# PMT_AMP_J000331REVH.net
KiCad netlist of a schematic drawn in EAGLE
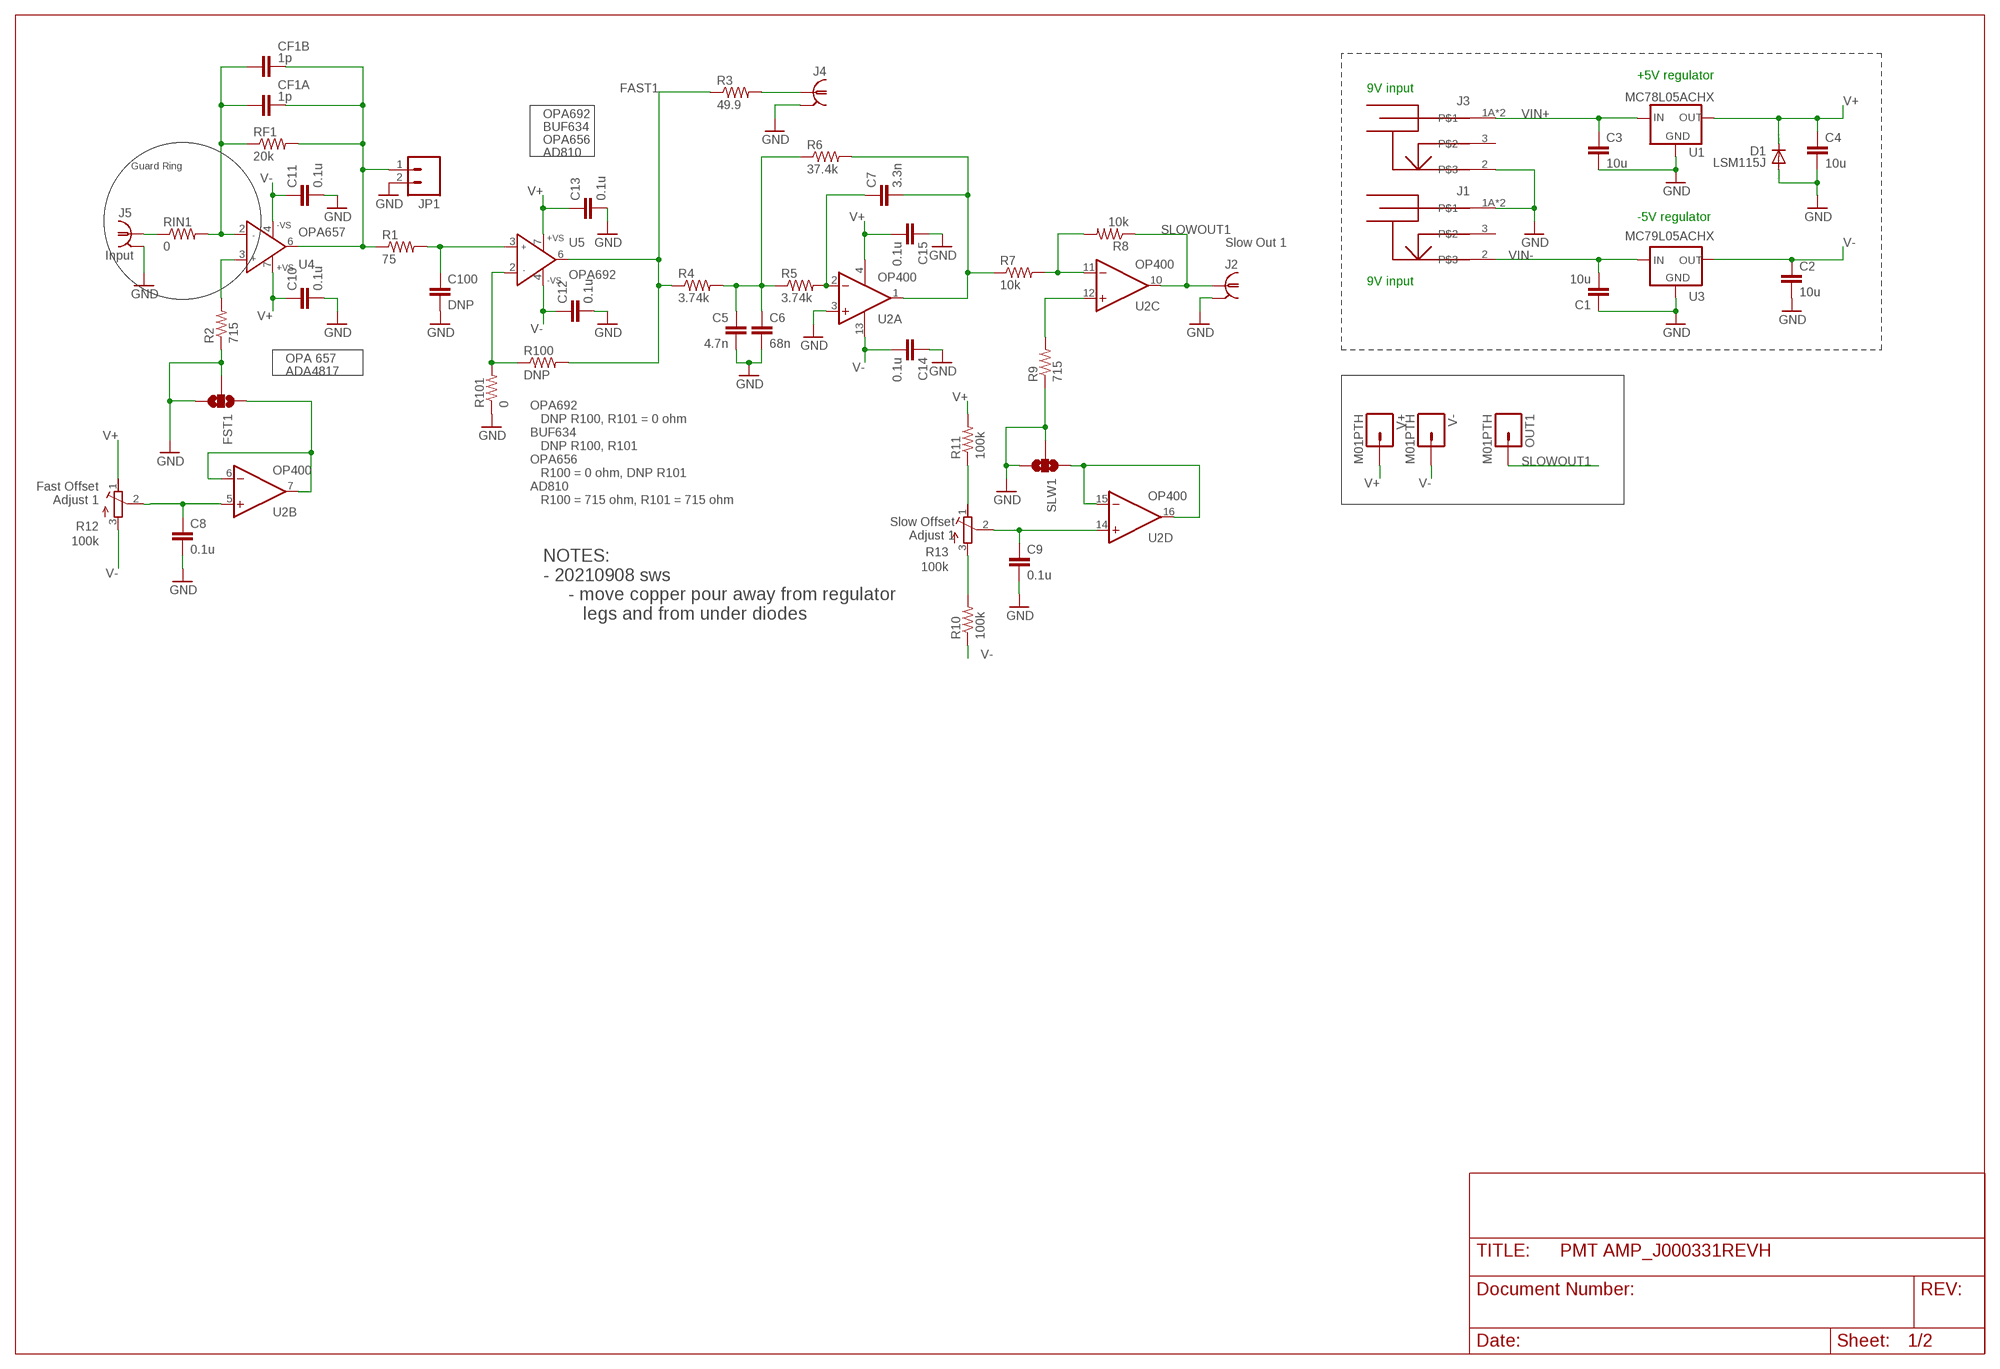
[diagram p0: schematic, sheet 1]
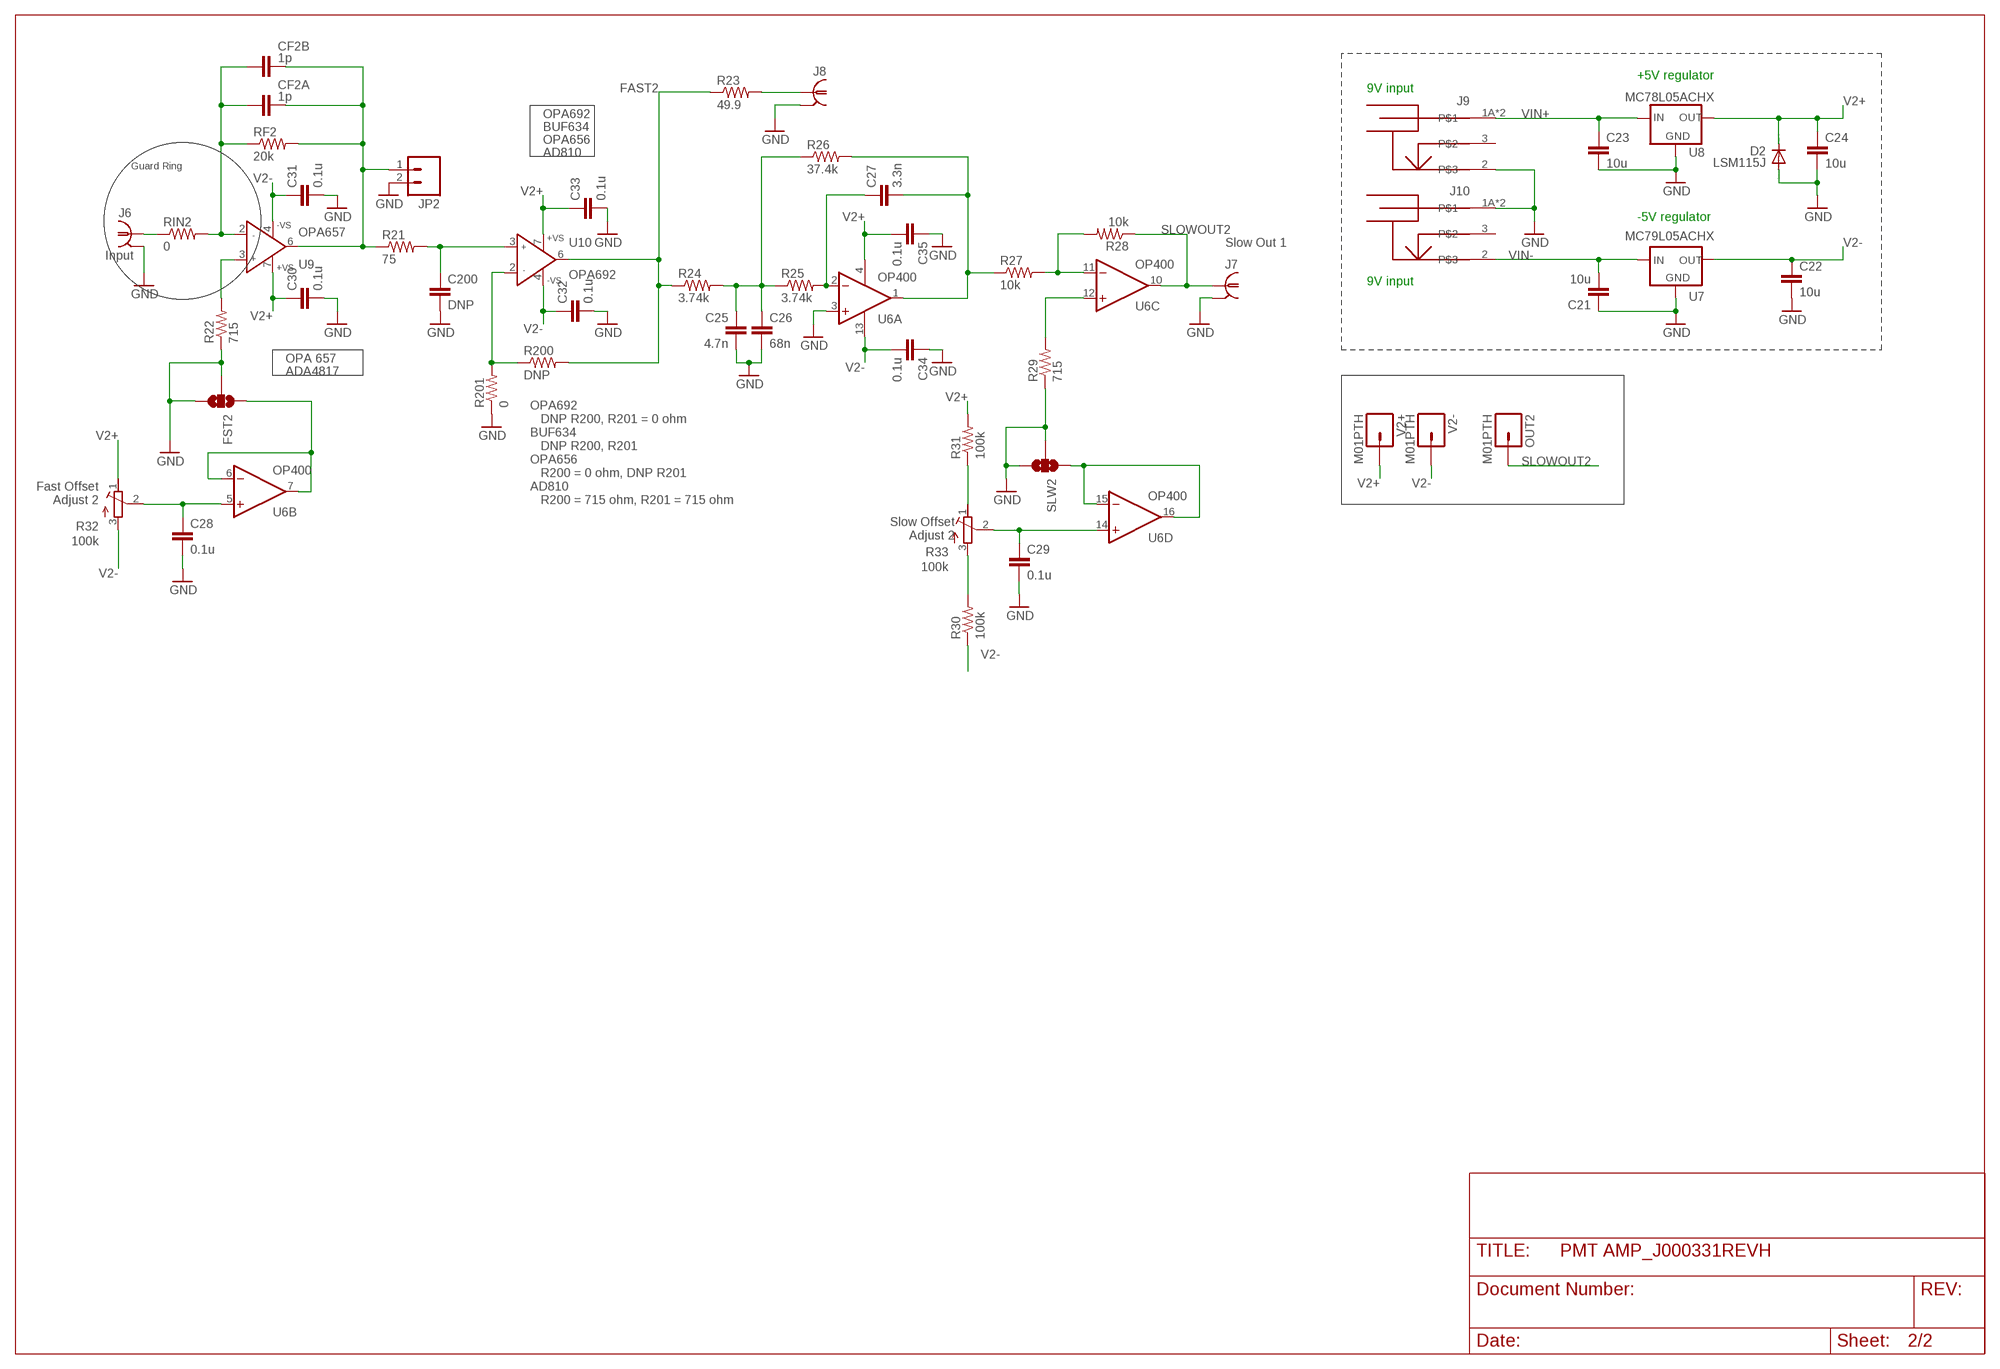
[diagram p1: schematic, sheet 2]

(export (version "E")
  (design (tool "Eeschema 10.0.6"))
  (components
    (comp (ref "C21")
      (value "10u")
      (footprint "eagle-import:C1206")
      (libsource (lib "eagle-import") (part "C-EUC1206"))
    )
    (comp (ref "C22")
      (value "10u")
      (footprint "eagle-import:C1206")
      (libsource (lib "eagle-import") (part "C-EUC1206"))
    )
    (comp (ref "C23")
      (value "10u")
      (footprint "eagle-import:C1206")
      (libsource (lib "eagle-import") (part "C-EUC1206"))
    )
    (comp (ref "C24")
      (value "10u")
      (footprint "eagle-import:C1206")
      (libsource (lib "eagle-import") (part "C-EUC1206"))
    )
    (comp (ref "C25")
      (value "4.7n")
      (footprint "eagle-import:C0805")
      (libsource (lib "eagle-import") (part "C-EUC0805"))
    )
    (comp (ref "C26")
      (value "68n")
      (footprint "eagle-import:C0805")
      (libsource (lib "eagle-import") (part "C-EUC0805"))
    )
    (comp (ref "C27")
      (value "3.3n")
      (footprint "eagle-import:C0805")
      (libsource (lib "eagle-import") (part "C-EUC0805"))
    )
    (comp (ref "C28")
      (value "0.1u")
      (footprint "eagle-import:C0603")
      (libsource (lib "eagle-import") (part "C-EUC0603"))
    )
    (comp (ref "C29")
      (value "0.1u")
      (footprint "eagle-import:C0603")
      (libsource (lib "eagle-import") (part "C-EUC0603"))
    )
    (comp (ref "C30")
      (value "0.1u")
      (footprint "eagle-import:C0603")
      (libsource (lib "eagle-import") (part "C-EUC0603"))
    )
    (comp (ref "C31")
      (value "0.1u")
      (footprint "eagle-import:C0603")
      (libsource (lib "eagle-import") (part "C-EUC0603"))
    )
    (comp (ref "C32")
      (value "0.1u")
      (footprint "eagle-import:C0603")
      (libsource (lib "eagle-import") (part "C-EUC0603"))
    )
    (comp (ref "C33")
      (value "0.1u")
      (footprint "eagle-import:C0603")
      (libsource (lib "eagle-import") (part "C-EUC0603"))
    )
    (comp (ref "C34")
      (value "0.1u")
      (footprint "eagle-import:C0603")
      (libsource (lib "eagle-import") (part "C-EUC0603"))
    )
    (comp (ref "C35")
      (value "0.1u")
      (footprint "eagle-import:C0603")
      (libsource (lib "eagle-import") (part "C-EUC0603"))
    )
    (comp (ref "C200")
      (value "DNP")
      (footprint "eagle-import:C0805")
      (libsource (lib "eagle-import") (part "C-EUC0805"))
    )
    (comp (ref "CF2A")
      (value "1p")
      (footprint "eagle-import:C1206")
      (libsource (lib "eagle-import") (part "C-EUC1206"))
    )
    (comp (ref "CF2B")
      (value "1p")
      (footprint "eagle-import:C1206")
      (libsource (lib "eagle-import") (part "C-EUC1206"))
    )
    (comp (ref "D2")
      (value "LSM115J")
      (footprint "eagle-import:DO214BA")
      (libsource (lib "eagle-import") (part "DIODE-DO214BA"))
    )
    (comp (ref "FST2")
      (value "SOLDERJUMPER_2WAYS")
      (footprint "eagle-import:SJ_3")
      (libsource (lib "eagle-import") (part "SOLDERJUMPER_2WAYS"))
    )
    (comp (ref "J6")
      (value "1-227161-0")
      (footprint "eagle-import:AMP_227161")
      (fields
        (field (name "MF") "TYCO ELECTRONICS")
        (field (name "MPN") "1-227161")
        (field (name "MF_1") "TE")
        (field (name "MPN_1") "5413879-1")
      )
      (libsource (lib "eagle-import") (part "?2271611--0"))
    )
    (comp (ref "J7")
      (value "1-227161-0")
      (footprint "eagle-import:AMP_227161")
      (fields
        (field (name "MF") "TYCO ELECTRONICS")
        (field (name "MPN") "1-227161")
        (field (name "MF_1") "TE")
        (field (name "MPN_1") "5413879-1")
      )
      (libsource (lib "eagle-import") (part "?2271611--0"))
    )
    (comp (ref "J8")
      (value "1-227161-0")
      (footprint "eagle-import:AMP_227161")
      (fields
        (field (name "MF") "TYCO ELECTRONICS")
        (field (name "MPN") "1-227161")
        (field (name "MF_1") "TE")
        (field (name "MPN_1") "5413879-1")
      )
      (libsource (lib "eagle-import") (part "?2271611--0"))
    )
    (comp (ref "J9")
      (value "POWER_JACK_SHUNTPJ-002")
      (footprint "eagle-import:PJ-002")
      (libsource (lib "eagle-import") (part "POWER_JACK_SHUNTPJ-002"))
    )
    (comp (ref "J10")
      (value "POWER_JACK_SHUNTPJ-002")
      (footprint "eagle-import:PJ-002")
      (libsource (lib "eagle-import") (part "POWER_JACK_SHUNTPJ-002"))
    )
    (comp (ref "JP2")
      (value "M02LOCK")
      (footprint "eagle-import:1X02_LOCK")
      (libsource (lib "eagle-import") (part "M02LOCK"))
    )
    (comp (ref "OUT2")
      (value "M01PTH")
      (footprint "eagle-import:1X01")
      (libsource (lib "eagle-import") (part "M01PTH"))
    )
    (comp (ref "R21")
      (value "75")
      (footprint "eagle-import:R0805")
      (libsource (lib "eagle-import") (part "R-US_R0805"))
    )
    (comp (ref "R22")
      (value "715")
      (footprint "eagle-import:R0805")
      (libsource (lib "eagle-import") (part "R-US_R0805"))
    )
    (comp (ref "R23")
      (value "49.9")
      (footprint "eagle-import:2512LONG")
      (libsource (lib "eagle-import") (part "RESISTOR-POWER2512WIDE"))
    )
    (comp (ref "R24")
      (value "3.74k")
      (footprint "eagle-import:R0805")
      (libsource (lib "eagle-import") (part "R-US_R0805"))
    )
    (comp (ref "R25")
      (value "3.74k")
      (footprint "eagle-import:R0805")
      (libsource (lib "eagle-import") (part "R-US_R0805"))
    )
    (comp (ref "R26")
      (value "37.4k")
      (footprint "eagle-import:R0805")
      (libsource (lib "eagle-import") (part "R-US_R0805"))
    )
    (comp (ref "R27")
      (value "10k")
      (footprint "eagle-import:R0805")
      (libsource (lib "eagle-import") (part "R-US_R0805"))
    )
    (comp (ref "R28")
      (value "10k")
      (footprint "eagle-import:R0805")
      (libsource (lib "eagle-import") (part "R-US_R0805"))
    )
    (comp (ref "R29")
      (value "715")
      (footprint "eagle-import:R0805")
      (libsource (lib "eagle-import") (part "R-US_R0805"))
    )
    (comp (ref "R30")
      (value "100k")
      (footprint "eagle-import:R0805")
      (libsource (lib "eagle-import") (part "R-US_R0805"))
    )
    (comp (ref "R31")
      (value "100k")
      (footprint "eagle-import:R0805")
      (libsource (lib "eagle-import") (part "R-US_R0805"))
    )
    (comp (ref "R32")
      (value "100k")
      (footprint "eagle-import:RTRIM3006P")
      (fields (field (name "MF") "BOURNS") (field (name "MPN") "3006P-1-104LF"))
      (libsource (lib "eagle-import") (part "R-TRIMM3006P"))
    )
    (comp (ref "R33")
      (value "100k")
      (footprint "eagle-import:RTRIM3006P")
      (fields (field (name "MF") "BOURNS") (field (name "MPN") "3006P-1-104LF"))
      (libsource (lib "eagle-import") (part "R-TRIMM3006P"))
    )
    (comp (ref "R200")
      (value "DNP")
      (footprint "eagle-import:R0805")
      (libsource (lib "eagle-import") (part "R-US_R0805"))
    )
    (comp (ref "R201")
      (value "0")
      (footprint "eagle-import:R0805")
      (libsource (lib "eagle-import") (part "R-US_R0805"))
    )
    (comp (ref "RF2")
      (value "20k")
      (footprint "eagle-import:R1206")
      (libsource (lib "eagle-import") (part "resistor_R-US_R1206"))
    )
    (comp (ref "RIN2")
      (value "0")
      (footprint "eagle-import:R0805")
      (libsource (lib "eagle-import") (part "R-US_R0805"))
    )
    (comp (ref "SLW2")
      (value "SOLDERJUMPER_2WAYS")
      (footprint "eagle-import:SJ_3")
      (libsource (lib "eagle-import") (part "SOLDERJUMPER_2WAYS"))
    )
    (comp (ref "U6")
      (value "OP400")
      (footprint "eagle-import:SO16L")
      (libsource (lib "eagle-import") (part "OP400SO16_W"))
    )
    (comp (ref "U7")
      (value "MC79L05ACHX")
      (footprint "eagle-import:SOT89")
      (libsource (lib "eagle-import") (part "79LXXSOT89"))
    )
    (comp (ref "U8")
      (value "MC78L05ACHX")
      (footprint "eagle-import:SOT89")
      (libsource (lib "eagle-import") (part "78LXXSOT89"))
    )
    (comp (ref "U9")
      (value "OPA657")
      (footprint "eagle-import:SO8")
      (libsource (lib "eagle-import") (part "AD820R"))
    )
    (comp (ref "U10")
      (value "OPA692")
      (footprint "eagle-import:SO8")
      (libsource (lib "eagle-import") (part "AD820R"))
    )
    (comp (ref "V2+")
      (value "M01PTH")
      (footprint "eagle-import:1X01")
      (libsource (lib "eagle-import") (part "M01PTH"))
    )
    (comp (ref "V2-")
      (value "M01PTH")
      (footprint "eagle-import:1X01")
      (libsource (lib "eagle-import") (part "M01PTH"))
    )
    (comp (ref "C1")
      (value "10u")
      (footprint "eagle-import:C1206")
      (libsource (lib "eagle-import") (part "C-EUC1206"))
    )
    (comp (ref "C2")
      (value "10u")
      (footprint "eagle-import:C1206")
      (libsource (lib "eagle-import") (part "C-EUC1206"))
    )
    (comp (ref "C3")
      (value "10u")
      (footprint "eagle-import:C1206")
      (libsource (lib "eagle-import") (part "C-EUC1206"))
    )
    (comp (ref "C4")
      (value "10u")
      (footprint "eagle-import:C1206")
      (libsource (lib "eagle-import") (part "C-EUC1206"))
    )
    (comp (ref "C5")
      (value "4.7n")
      (footprint "eagle-import:C0805")
      (libsource (lib "eagle-import") (part "C-EUC0805"))
    )
    (comp (ref "C6")
      (value "68n")
      (footprint "eagle-import:C0805")
      (libsource (lib "eagle-import") (part "C-EUC0805"))
    )
    (comp (ref "C7")
      (value "3.3n")
      (footprint "eagle-import:C0805")
      (libsource (lib "eagle-import") (part "C-EUC0805"))
    )
    (comp (ref "C8")
      (value "0.1u")
      (footprint "eagle-import:C0603")
      (libsource (lib "eagle-import") (part "C-EUC0603"))
    )
    (comp (ref "C9")
      (value "0.1u")
      (footprint "eagle-import:C0603")
      (libsource (lib "eagle-import") (part "C-EUC0603"))
    )
    (comp (ref "C10")
      (value "0.1u")
      (footprint "eagle-import:C0603")
      (libsource (lib "eagle-import") (part "C-EUC0603"))
    )
    (comp (ref "C11")
      (value "0.1u")
      (footprint "eagle-import:C0603")
      (libsource (lib "eagle-import") (part "C-EUC0603"))
    )
    (comp (ref "C12")
      (value "0.1u")
      (footprint "eagle-import:C0603")
      (libsource (lib "eagle-import") (part "C-EUC0603"))
    )
    (comp (ref "C13")
      (value "0.1u")
      (footprint "eagle-import:C0603")
      (libsource (lib "eagle-import") (part "C-EUC0603"))
    )
    (comp (ref "C14")
      (value "0.1u")
      (footprint "eagle-import:C0603")
      (libsource (lib "eagle-import") (part "C-EUC0603"))
    )
    (comp (ref "C15")
      (value "0.1u")
      (footprint "eagle-import:C0603")
      (libsource (lib "eagle-import") (part "C-EUC0603"))
    )
    (comp (ref "C100")
      (value "DNP")
      (footprint "eagle-import:C0805")
      (libsource (lib "eagle-import") (part "C-EUC0805"))
    )
    (comp (ref "CF1A")
      (value "1p")
      (footprint "eagle-import:C1206")
      (libsource (lib "eagle-import") (part "C-EUC1206"))
    )
    (comp (ref "CF1B")
      (value "1p")
      (footprint "eagle-import:C1206")
      (libsource (lib "eagle-import") (part "C-EUC1206"))
    )
    (comp (ref "D1")
      (value "LSM115J")
      (footprint "eagle-import:DO214BA")
      (libsource (lib "eagle-import") (part "DIODE-DO214BA"))
    )
    (comp (ref "FST1")
      (value "SOLDERJUMPER_2WAYS")
      (footprint "eagle-import:SJ_3")
      (libsource (lib "eagle-import") (part "SOLDERJUMPER_2WAYS"))
    )
    (comp (ref "J1")
      (value "POWER_JACK_SHUNTPJ-002")
      (footprint "eagle-import:PJ-002")
      (libsource (lib "eagle-import") (part "POWER_JACK_SHUNTPJ-002"))
    )
    (comp (ref "J2")
      (value "1-227161-0")
      (footprint "eagle-import:AMP_227161")
      (fields
        (field (name "MF") "TYCO ELECTRONICS")
        (field (name "MPN") "1-227161")
        (field (name "MF_1") "TE")
        (field (name "MPN_1") "5413879-1")
      )
      (libsource (lib "eagle-import") (part "?2271611--0"))
    )
    (comp (ref "J3")
      (value "POWER_JACK_SHUNTPJ-002")
      (footprint "eagle-import:PJ-002")
      (libsource (lib "eagle-import") (part "POWER_JACK_SHUNTPJ-002"))
    )
    (comp (ref "J4")
      (value "1-227161-0")
      (footprint "eagle-import:AMP_227161")
      (fields
        (field (name "MF") "TYCO ELECTRONICS")
        (field (name "MPN") "1-227161")
        (field (name "MF_1") "TE")
        (field (name "MPN_1") "5413879-1")
      )
      (libsource (lib "eagle-import") (part "?2271611--0"))
    )
    (comp (ref "J5")
      (value "1-227161-0")
      (footprint "eagle-import:AMP_227161")
      (fields
        (field (name "MF") "TYCO ELECTRONICS")
        (field (name "MPN") "1-227161")
        (field (name "MF_1") "TE")
        (field (name "MPN_1") "5413879-1")
      )
      (libsource (lib "eagle-import") (part "?2271611--0"))
    )
    (comp (ref "JP1")
      (value "M02LOCK")
      (footprint "eagle-import:1X02_LOCK")
      (libsource (lib "eagle-import") (part "M02LOCK"))
    )
    (comp (ref "OUT1")
      (value "M01PTH")
      (footprint "eagle-import:1X01")
      (libsource (lib "eagle-import") (part "M01PTH"))
    )
    (comp (ref "R1")
      (value "75")
      (footprint "eagle-import:R0805")
      (libsource (lib "eagle-import") (part "R-US_R0805"))
    )
    (comp (ref "R2")
      (value "715")
      (footprint "eagle-import:R0805")
      (libsource (lib "eagle-import") (part "R-US_R0805"))
    )
    (comp (ref "R3")
      (value "49.9")
      (footprint "eagle-import:2512LONG")
      (libsource (lib "eagle-import") (part "RESISTOR-POWER2512WIDE"))
    )
    (comp (ref "R4")
      (value "3.74k")
      (footprint "eagle-import:R0805")
      (libsource (lib "eagle-import") (part "R-US_R0805"))
    )
    (comp (ref "R5")
      (value "3.74k")
      (footprint "eagle-import:R0805")
      (libsource (lib "eagle-import") (part "R-US_R0805"))
    )
    (comp (ref "R6")
      (value "37.4k")
      (footprint "eagle-import:R0805")
      (libsource (lib "eagle-import") (part "R-US_R0805"))
    )
    (comp (ref "R7")
      (value "10k")
      (footprint "eagle-import:R0805")
      (libsource (lib "eagle-import") (part "R-US_R0805"))
    )
    (comp (ref "R8")
      (value "10k")
      (footprint "eagle-import:R0805")
      (libsource (lib "eagle-import") (part "R-US_R0805"))
    )
    (comp (ref "R9")
      (value "715")
      (footprint "eagle-import:R0805")
      (libsource (lib "eagle-import") (part "R-US_R0805"))
    )
    (comp (ref "R10")
      (value "100k")
      (footprint "eagle-import:R0805")
      (libsource (lib "eagle-import") (part "R-US_R0805"))
    )
    (comp (ref "R11")
      (value "100k")
      (footprint "eagle-import:R0805")
      (libsource (lib "eagle-import") (part "R-US_R0805"))
    )
    (comp (ref "R12")
      (value "100k")
      (footprint "eagle-import:RTRIM3006P")
      (fields (field (name "MF") "BOURNS") (field (name "MPN") "3006P-1-104LF"))
      (libsource (lib "eagle-import") (part "R-TRIMM3006P"))
    )
    (comp (ref "R13")
      (value "100k")
      (footprint "eagle-import:RTRIM3006P")
      (fields (field (name "MF") "BOURNS") (field (name "MPN") "3006P-1-104LF"))
      (libsource (lib "eagle-import") (part "R-TRIMM3006P"))
    )
    (comp (ref "R100")
      (value "DNP")
      (footprint "eagle-import:R0805")
      (libsource (lib "eagle-import") (part "R-US_R0805"))
    )
    (comp (ref "R101")
      (value "0")
      (footprint "eagle-import:R0805")
      (libsource (lib "eagle-import") (part "R-US_R0805"))
    )
    (comp (ref "RF1")
      (value "20k")
      (footprint "eagle-import:R1206")
      (libsource (lib "eagle-import") (part "resistor_R-US_R1206"))
    )
    (comp (ref "RIN1")
      (value "0")
      (footprint "eagle-import:R0805")
      (libsource (lib "eagle-import") (part "R-US_R0805"))
    )
    (comp (ref "SLW1")
      (value "SOLDERJUMPER_2WAYS")
      (footprint "eagle-import:SJ_3")
      (libsource (lib "eagle-import") (part "SOLDERJUMPER_2WAYS"))
    )
    (comp (ref "U1")
      (value "MC78L05ACHX")
      (footprint "eagle-import:SOT89")
      (libsource (lib "eagle-import") (part "78LXXSOT89"))
    )
    (comp (ref "U2")
      (value "OP400")
      (footprint "eagle-import:SO16L")
      (libsource (lib "eagle-import") (part "OP400SO16_W"))
    )
    (comp (ref "U3")
      (value "MC79L05ACHX")
      (footprint "eagle-import:SOT89")
      (libsource (lib "eagle-import") (part "79LXXSOT89"))
    )
    (comp (ref "U4")
      (value "OPA657")
      (footprint "eagle-import:SO8")
      (libsource (lib "eagle-import") (part "AD820R"))
    )
    (comp (ref "U5")
      (value "OPA692")
      (footprint "eagle-import:SO8")
      (libsource (lib "eagle-import") (part "AD820R"))
    )
    (comp (ref "V+")
      (value "M01PTH")
      (footprint "eagle-import:1X01")
      (libsource (lib "eagle-import") (part "M01PTH"))
    )
    (comp (ref "V-")
      (value "M01PTH")
      (footprint "eagle-import:1X01")
      (libsource (lib "eagle-import") (part "M01PTH"))
    )
  )
  (nets
    (net (code "1") (name "FAST1") (class "Default")
      (node (ref "R100") (pin "2") (pinfunction "2_2") (pintype "passive"))
      (node (ref "R3") (pin "1") (pinfunction "1_1") (pintype "passive"))
      (node (ref "R4") (pin "1") (pinfunction "1_1") (pintype "passive"))
      (node (ref "U5") (pin "6") (pinfunction "OUT_6") (pintype "output"))
    )
    (net (code "2") (name "FAST2") (class "Default")
      (node (ref "R200") (pin "2") (pinfunction "2_2") (pintype "passive"))
      (node (ref "R23") (pin "1") (pinfunction "1_1") (pintype "passive"))
      (node (ref "R24") (pin "1") (pinfunction "1_1") (pintype "passive"))
      (node (ref "U10") (pin "6") (pinfunction "OUT_6") (pintype "output"))
    )
    (net (code "3") (name "GND") (class "Default")
      (node (ref "C1") (pin "1") (pinfunction "1_1") (pintype "passive"))
      (node (ref "C10") (pin "2") (pinfunction "2_2") (pintype "passive"))
      (node (ref "C100") (pin "2") (pinfunction "2_2") (pintype "passive"))
      (node (ref "C11") (pin "2") (pinfunction "2_2") (pintype "passive"))
      (node (ref "C12") (pin "2") (pinfunction "2_2") (pintype "passive"))
      (node (ref "C13") (pin "2") (pinfunction "2_2") (pintype "passive"))
      (node (ref "C14") (pin "1") (pinfunction "1_1") (pintype "passive"))
      (node (ref "C15") (pin "1") (pinfunction "1_1") (pintype "passive"))
      (node (ref "C2") (pin "2") (pinfunction "2_2") (pintype "passive"))
      (node (ref "C200") (pin "2") (pinfunction "2_2") (pintype "passive"))
      (node (ref "C21") (pin "1") (pinfunction "1_1") (pintype "passive"))
      (node (ref "C22") (pin "2") (pinfunction "2_2") (pintype "passive"))
      (node (ref "C23") (pin "2") (pinfunction "2_2") (pintype "passive"))
      (node (ref "C24") (pin "2") (pinfunction "2_2") (pintype "passive"))
      (node (ref "C25") (pin "2") (pinfunction "2_2") (pintype "passive"))
      (node (ref "C26") (pin "2") (pinfunction "2_2") (pintype "passive"))
      (node (ref "C28") (pin "2") (pinfunction "2_2") (pintype "passive"))
      (node (ref "C29") (pin "2") (pinfunction "2_2") (pintype "passive"))
      (node (ref "C3") (pin "2") (pinfunction "2_2") (pintype "passive"))
      (node (ref "C30") (pin "2") (pinfunction "2_2") (pintype "passive"))
      (node (ref "C31") (pin "2") (pinfunction "2_2") (pintype "passive"))
      (node (ref "C32") (pin "2") (pinfunction "2_2") (pintype "passive"))
      (node (ref "C33") (pin "2") (pinfunction "2_2") (pintype "passive"))
      (node (ref "C34") (pin "1") (pinfunction "1_1") (pintype "passive"))
      (node (ref "C35") (pin "1") (pinfunction "1_1") (pintype "passive"))
      (node (ref "C4") (pin "2") (pinfunction "2_2") (pintype "passive"))
      (node (ref "C5") (pin "2") (pinfunction "2_2") (pintype "passive"))
      (node (ref "C6") (pin "2") (pinfunction "2_2") (pintype "passive"))
      (node (ref "C8") (pin "2") (pinfunction "2_2") (pintype "passive"))
      (node (ref "C9") (pin "2") (pinfunction "2_2") (pintype "passive"))
      (node (ref "D1") (pin "A") (pinfunction "A_A") (pintype "passive"))
      (node (ref "D2") (pin "A") (pinfunction "A_A") (pintype "passive"))
      (node (ref "FST1") (pin "2") (pinfunction "2_2") (pintype "passive"))
      (node (ref "FST1") (pin "3") (pinfunction "3_3") (pintype "passive"))
      (node (ref "FST2") (pin "2") (pinfunction "2_2") (pintype "passive"))
      (node (ref "FST2") (pin "3") (pinfunction "3_3") (pintype "passive"))
      (node (ref "J1") (pin "1A") (pinfunction "P$1_1A") (pintype "bidirectional"))
      (node (ref "J1") (pin "1B") (pinfunction "P$1_1B") (pintype "bidirectional"))
      (node (ref "J10") (pin "1A") (pinfunction "P$1_1A") (pintype "bidirectional"))
      (node (ref "J10") (pin "1B") (pinfunction "P$1_1B") (pintype "bidirectional"))
      (node (ref "J2") (pin "2") (pinfunction "GND_2") (pintype "power_in"))
      (node (ref "J3") (pin "2") (pinfunction "P$3_2") (pintype "bidirectional"))
      (node (ref "J4") (pin "2") (pinfunction "GND_2") (pintype "power_in"))
      (node (ref "J5") (pin "2") (pinfunction "GND_2") (pintype "power_in"))
      (node (ref "J6") (pin "2") (pinfunction "GND_2") (pintype "power_in"))
      (node (ref "J7") (pin "2") (pinfunction "GND_2") (pintype "power_in"))
      (node (ref "J8") (pin "2") (pinfunction "GND_2") (pintype "power_in"))
      (node (ref "J9") (pin "2") (pinfunction "P$3_2") (pintype "bidirectional"))
      (node (ref "JP1") (pin "2") (pinfunction "2_2") (pintype "passive"))
      (node (ref "JP2") (pin "2") (pinfunction "2_2") (pintype "passive"))
      (node (ref "R101") (pin "1") (pinfunction "1_1") (pintype "passive"))
      (node (ref "R2") (pin "1") (pinfunction "1_1") (pintype "passive"))
      (node (ref "R201") (pin "1") (pinfunction "1_1") (pintype "passive"))
      (node (ref "R22") (pin "1") (pinfunction "1_1") (pintype "passive"))
      (node (ref "R29") (pin "1") (pinfunction "1_1") (pintype "passive"))
      (node (ref "R9") (pin "1") (pinfunction "1_1") (pintype "passive"))
      (node (ref "SLW1") (pin "2") (pinfunction "2_2") (pintype "passive"))
      (node (ref "SLW1") (pin "3") (pinfunction "3_3") (pintype "passive"))
      (node (ref "SLW2") (pin "2") (pinfunction "2_2") (pintype "passive"))
      (node (ref "SLW2") (pin "3") (pinfunction "3_3") (pintype "passive"))
      (node (ref "U1") (pin "2") (pinfunction "GND_2") (pintype "input"))
      (node (ref "U1") (pin "2@1") (pinfunction "GND_2@1") (pintype "input"))
      (node (ref "U2") (pin "3") (pinfunction "+IN_3") (pintype "input"))
      (node (ref "U3") (pin "1") (pinfunction "GND_1") (pintype "input"))
      (node (ref "U6") (pin "3") (pinfunction "+IN_3") (pintype "input"))
      (node (ref "U7") (pin "1") (pinfunction "GND_1") (pintype "input"))
      (node (ref "U8") (pin "2") (pinfunction "GND_2") (pintype "input"))
      (node (ref "U8") (pin "2@1") (pinfunction "GND_2@1") (pintype "input"))
    )
    (net (code "4") (name "Net-(C5-Pad1)") (class "Default")
      (node (ref "C5") (pin "1") (pinfunction "1_1") (pintype "passive"))
      (node (ref "C6") (pin "1") (pinfunction "1_1") (pintype "passive"))
      (node (ref "R4") (pin "2") (pinfunction "2_2") (pintype "passive"))
      (node (ref "R5") (pin "1") (pinfunction "1_1") (pintype "passive"))
      (node (ref "R6") (pin "1") (pinfunction "1_1") (pintype "passive"))
    )
    (net (code "5") (name "Net-(C25-Pad1)") (class "Default")
      (node (ref "C25") (pin "1") (pinfunction "1_1") (pintype "passive"))
      (node (ref "C26") (pin "1") (pinfunction "1_1") (pintype "passive"))
      (node (ref "R24") (pin "2") (pinfunction "2_2") (pintype "passive"))
      (node (ref "R25") (pin "1") (pinfunction "1_1") (pintype "passive"))
      (node (ref "R26") (pin "1") (pinfunction "1_1") (pintype "passive"))
    )
    (net (code "6") (name "Net-(J4-Pad1)") (class "Default")
      (node (ref "J4") (pin "1") (pinfunction "1_1") (pintype "passive"))
      (node (ref "R3") (pin "2") (pinfunction "2_2") (pintype "passive"))
    )
    (net (code "7") (name "Net-(J5-Pad1)") (class "Default")
      (node (ref "J5") (pin "1") (pinfunction "1_1") (pintype "passive"))
      (node (ref "RIN1") (pin "1") (pinfunction "1_1") (pintype "passive"))
    )
    (net (code "8") (name "Net-(J6-Pad1)") (class "Default")
      (node (ref "J6") (pin "1") (pinfunction "1_1") (pintype "passive"))
      (node (ref "RIN2") (pin "1") (pinfunction "1_1") (pintype "passive"))
    )
    (net (code "9") (name "Net-(J8-Pad1)") (class "Default")
      (node (ref "J8") (pin "1") (pinfunction "1_1") (pintype "passive"))
      (node (ref "R23") (pin "2") (pinfunction "2_2") (pintype "passive"))
    )
    (net (code "10") (name "Net-(R12-S)") (class "Default")
      (node (ref "C8") (pin "1") (pinfunction "1_1") (pintype "passive"))
      (node (ref "R12") (pin "2") (pinfunction "S_2") (pintype "passive"))
      (node (ref "U2") (pin "5") (pinfunction "+IN_5") (pintype "input"))
    )
    (net (code "11") (name "Net-(R13-A)") (class "Default")
      (node (ref "R10") (pin "2") (pinfunction "2_2") (pintype "passive"))
      (node (ref "R13") (pin "3") (pinfunction "A_3") (pintype "passive"))
    )
    (net (code "12") (name "Net-(R13-E)") (class "Default")
      (node (ref "R11") (pin "1") (pinfunction "1_1") (pintype "passive"))
      (node (ref "R13") (pin "1") (pinfunction "E_1") (pintype "passive"))
    )
    (net (code "13") (name "Net-(R13-S)") (class "Default")
      (node (ref "C9") (pin "1") (pinfunction "1_1") (pintype "passive"))
      (node (ref "R13") (pin "2") (pinfunction "S_2") (pintype "passive"))
      (node (ref "U2") (pin "14") (pinfunction "+IN_14") (pintype "input"))
    )
    (net (code "14") (name "Net-(R32-S)") (class "Default")
      (node (ref "C28") (pin "1") (pinfunction "1_1") (pintype "passive"))
      (node (ref "R32") (pin "2") (pinfunction "S_2") (pintype "passive"))
      (node (ref "U6") (pin "5") (pinfunction "+IN_5") (pintype "input"))
    )
    (net (code "15") (name "Net-(R33-A)") (class "Default")
      (node (ref "R30") (pin "2") (pinfunction "2_2") (pintype "passive"))
      (node (ref "R33") (pin "3") (pinfunction "A_3") (pintype "passive"))
    )
    (net (code "16") (name "Net-(R33-E)") (class "Default")
      (node (ref "R31") (pin "1") (pinfunction "1_1") (pintype "passive"))
      (node (ref "R33") (pin "1") (pinfunction "E_1") (pintype "passive"))
    )
    (net (code "17") (name "Net-(R33-S)") (class "Default")
      (node (ref "C29") (pin "1") (pinfunction "1_1") (pintype "passive"))
      (node (ref "R33") (pin "2") (pinfunction "S_2") (pintype "passive"))
      (node (ref "U6") (pin "14") (pinfunction "+IN_14") (pintype "input"))
    )
    (net (code "18") (name "Net-(U2A--IN)") (class "Default")
      (node (ref "C7") (pin "1") (pinfunction "1_1") (pintype "passive"))
      (node (ref "R5") (pin "2") (pinfunction "2_2") (pintype "passive"))
      (node (ref "U2") (pin "2") (pinfunction "-IN_2") (pintype "input"))
    )
    (net (code "19") (name "Net-(U2A-OUT)") (class "Default")
      (node (ref "C7") (pin "2") (pinfunction "2_2") (pintype "passive"))
      (node (ref "R6") (pin "2") (pinfunction "2_2") (pintype "passive"))
      (node (ref "R7") (pin "1") (pinfunction "1_1") (pintype "passive"))
      (node (ref "U2") (pin "1") (pinfunction "OUT_1") (pintype "output"))
    )
    (net (code "20") (name "Net-(U2B--IN)") (class "Default")
      (node (ref "FST1") (pin "1") (pinfunction "1_1") (pintype "passive"))
      (node (ref "U2") (pin "6") (pinfunction "-IN_6") (pintype "input"))
      (node (ref "U2") (pin "7") (pinfunction "OUT_7") (pintype "output"))
    )
    (net (code "21") (name "Net-(U2C-+IN)") (class "Default")
      (node (ref "R9") (pin "2") (pinfunction "2_2") (pintype "passive"))
      (node (ref "U2") (pin "12") (pinfunction "+IN_12") (pintype "input"))
    )
    (net (code "22") (name "Net-(U2C--IN)") (class "Default")
      (node (ref "R7") (pin "2") (pinfunction "2_2") (pintype "passive"))
      (node (ref "R8") (pin "2") (pinfunction "2_2") (pintype "passive"))
      (node (ref "U2") (pin "11") (pinfunction "-IN_11") (pintype "input"))
    )
    (net (code "23") (name "Net-(U2D--IN)") (class "Default")
      (node (ref "SLW1") (pin "1") (pinfunction "1_1") (pintype "passive"))
      (node (ref "U2") (pin "15") (pinfunction "-IN_15") (pintype "input"))
      (node (ref "U2") (pin "16") (pinfunction "OUT_16") (pintype "output"))
    )
    (net (code "24") (name "Net-(U4-IN+)") (class "Default")
      (node (ref "R2") (pin "2") (pinfunction "2_2") (pintype "passive"))
      (node (ref "U4") (pin "3") (pinfunction "IN+_3") (pintype "input"))
    )
    (net (code "25") (name "Net-(U4-IN-)") (class "Default")
      (node (ref "CF1A") (pin "1") (pinfunction "1_1") (pintype "passive"))
      (node (ref "CF1B") (pin "1") (pinfunction "1_1") (pintype "passive"))
      (node (ref "RF1") (pin "1") (pinfunction "1_1") (pintype "passive"))
      (node (ref "RIN1") (pin "2") (pinfunction "2_2") (pintype "passive"))
      (node (ref "U4") (pin "2") (pinfunction "IN-_2") (pintype "input"))
    )
    (net (code "26") (name "Net-(U4-OUT)") (class "Default")
      (node (ref "CF1A") (pin "2") (pinfunction "2_2") (pintype "passive"))
      (node (ref "CF1B") (pin "2") (pinfunction "2_2") (pintype "passive"))
      (node (ref "JP1") (pin "1") (pinfunction "1_1") (pintype "passive"))
      (node (ref "R1") (pin "1") (pinfunction "1_1") (pintype "passive"))
      (node (ref "RF1") (pin "2") (pinfunction "2_2") (pintype "passive"))
      (node (ref "U4") (pin "6") (pinfunction "OUT_6") (pintype "output"))
    )
    (net (code "27") (name "Net-(U5-IN+)") (class "Default")
      (node (ref "C100") (pin "1") (pinfunction "1_1") (pintype "passive"))
      (node (ref "R1") (pin "2") (pinfunction "2_2") (pintype "passive"))
      (node (ref "U5") (pin "3") (pinfunction "IN+_3") (pintype "input"))
    )
    (net (code "28") (name "Net-(U5-IN-)") (class "Default")
      (node (ref "R100") (pin "1") (pinfunction "1_1") (pintype "passive"))
      (node (ref "R101") (pin "2") (pinfunction "2_2") (pintype "passive"))
      (node (ref "U5") (pin "2") (pinfunction "IN-_2") (pintype "input"))
    )
    (net (code "29") (name "Net-(U6A--IN)") (class "Default")
      (node (ref "C27") (pin "1") (pinfunction "1_1") (pintype "passive"))
      (node (ref "R25") (pin "2") (pinfunction "2_2") (pintype "passive"))
      (node (ref "U6") (pin "2") (pinfunction "-IN_2") (pintype "input"))
    )
    (net (code "30") (name "Net-(U6A-OUT)") (class "Default")
      (node (ref "C27") (pin "2") (pinfunction "2_2") (pintype "passive"))
      (node (ref "R26") (pin "2") (pinfunction "2_2") (pintype "passive"))
      (node (ref "R27") (pin "1") (pinfunction "1_1") (pintype "passive"))
      (node (ref "U6") (pin "1") (pinfunction "OUT_1") (pintype "output"))
    )
    (net (code "31") (name "Net-(U6B--IN)") (class "Default")
      (node (ref "FST2") (pin "1") (pinfunction "1_1") (pintype "passive"))
      (node (ref "U6") (pin "6") (pinfunction "-IN_6") (pintype "input"))
      (node (ref "U6") (pin "7") (pinfunction "OUT_7") (pintype "output"))
    )
    (net (code "32") (name "Net-(U6C-+IN)") (class "Default")
      (node (ref "R29") (pin "2") (pinfunction "2_2") (pintype "passive"))
      (node (ref "U6") (pin "12") (pinfunction "+IN_12") (pintype "input"))
    )
    (net (code "33") (name "Net-(U6C--IN)") (class "Default")
      (node (ref "R27") (pin "2") (pinfunction "2_2") (pintype "passive"))
      (node (ref "R28") (pin "2") (pinfunction "2_2") (pintype "passive"))
      (node (ref "U6") (pin "11") (pinfunction "-IN_11") (pintype "input"))
    )
    (net (code "34") (name "Net-(U6D--IN)") (class "Default")
      (node (ref "SLW2") (pin "1") (pinfunction "1_1") (pintype "passive"))
      (node (ref "U6") (pin "15") (pinfunction "-IN_15") (pintype "input"))
      (node (ref "U6") (pin "16") (pinfunction "OUT_16") (pintype "output"))
    )
    (net (code "35") (name "Net-(U9-IN+)") (class "Default")
      (node (ref "R22") (pin "2") (pinfunction "2_2") (pintype "passive"))
      (node (ref "U9") (pin "3") (pinfunction "IN+_3") (pintype "input"))
    )
    (net (code "36") (name "Net-(U9-IN-)") (class "Default")
      (node (ref "CF2A") (pin "1") (pinfunction "1_1") (pintype "passive"))
      (node (ref "CF2B") (pin "1") (pinfunction "1_1") (pintype "passive"))
      (node (ref "RF2") (pin "1") (pinfunction "1_1") (pintype "passive"))
      (node (ref "RIN2") (pin "2") (pinfunction "2_2") (pintype "passive"))
      (node (ref "U9") (pin "2") (pinfunction "IN-_2") (pintype "input"))
    )
    (net (code "37") (name "Net-(U9-OUT)") (class "Default")
      (node (ref "CF2A") (pin "2") (pinfunction "2_2") (pintype "passive"))
      (node (ref "CF2B") (pin "2") (pinfunction "2_2") (pintype "passive"))
      (node (ref "JP2") (pin "1") (pinfunction "1_1") (pintype "passive"))
      (node (ref "R21") (pin "1") (pinfunction "1_1") (pintype "passive"))
      (node (ref "RF2") (pin "2") (pinfunction "2_2") (pintype "passive"))
      (node (ref "U9") (pin "6") (pinfunction "OUT_6") (pintype "output"))
    )
    (net (code "38") (name "Net-(U10-IN+)") (class "Default")
      (node (ref "C200") (pin "1") (pinfunction "1_1") (pintype "passive"))
      (node (ref "R21") (pin "2") (pinfunction "2_2") (pintype "passive"))
      (node (ref "U10") (pin "3") (pinfunction "IN+_3") (pintype "input"))
    )
    (net (code "39") (name "Net-(U10-IN-)") (class "Default")
      (node (ref "R200") (pin "1") (pinfunction "1_1") (pintype "passive"))
      (node (ref "R201") (pin "2") (pinfunction "2_2") (pintype "passive"))
      (node (ref "U10") (pin "2") (pinfunction "IN-_2") (pintype "input"))
    )
    (net (code "40") (name "SLOWOUT1") (class "Default")
      (node (ref "J2") (pin "1") (pinfunction "1_1") (pintype "passive"))
      (node (ref "OUT1") (pin "1") (pinfunction "1_1") (pintype "passive"))
      (node (ref "R8") (pin "1") (pinfunction "1_1") (pintype "passive"))
      (node (ref "U2") (pin "10") (pinfunction "OUT_10") (pintype "output"))
    )
    (net (code "41") (name "SLOWOUT2") (class "Default")
      (node (ref "J7") (pin "1") (pinfunction "1_1") (pintype "passive"))
      (node (ref "OUT2") (pin "1") (pinfunction "1_1") (pintype "passive"))
      (node (ref "R28") (pin "1") (pinfunction "1_1") (pintype "passive"))
      (node (ref "U6") (pin "10") (pinfunction "OUT_10") (pintype "output"))
    )
    (net (code "42") (name "V+") (class "Default")
      (node (ref "C10") (pin "1") (pinfunction "1_1") (pintype "passive"))
      (node (ref "C13") (pin "1") (pinfunction "1_1") (pintype "passive"))
      (node (ref "C15") (pin "2") (pinfunction "2_2") (pintype "passive"))
      (node (ref "C4") (pin "1") (pinfunction "1_1") (pintype "passive"))
      (node (ref "D1") (pin "C") (pinfunction "C_C") (pintype "passive"))
      (node (ref "R11") (pin "2") (pinfunction "2_2") (pintype "passive"))
      (node (ref "R12") (pin "1") (pinfunction "E_1") (pintype "passive"))
      (node (ref "U1") (pin "1") (pinfunction "OUT_1") (pintype "passive"))
      (node (ref "U2") (pin "4") (pinfunction "V+_4") (pintype "power_in"))
      (node (ref "U4") (pin "7") (pinfunction "+VS_7") (pintype "input"))
      (node (ref "U5") (pin "7") (pinfunction "+VS_7") (pintype "input"))
      (node (ref "V+") (pin "1") (pinfunction "1_1") (pintype "passive"))
    )
    (net (code "43") (name "V-") (class "Default")
      (node (ref "C11") (pin "1") (pinfunction "1_1") (pintype "passive"))
      (node (ref "C12") (pin "1") (pinfunction "1_1") (pintype "passive"))
      (node (ref "C14") (pin "2") (pinfunction "2_2") (pintype "passive"))
      (node (ref "C2") (pin "1") (pinfunction "1_1") (pintype "passive"))
      (node (ref "R10") (pin "1") (pinfunction "1_1") (pintype "passive"))
      (node (ref "R12") (pin "3") (pinfunction "A_3") (pintype "passive"))
      (node (ref "U2") (pin "13") (pinfunction "V-_13") (pintype "power_in"))
      (node (ref "U3") (pin "3") (pinfunction "OUT_3") (pintype "passive"))
      (node (ref "U4") (pin "4") (pinfunction "-VS_4") (pintype "input"))
      (node (ref "U5") (pin "4") (pinfunction "-VS_4") (pintype "input"))
      (node (ref "V-") (pin "1") (pinfunction "1_1") (pintype "passive"))
    )
    (net (code "44") (name "V2+") (class "Default")
      (node (ref "C24") (pin "1") (pinfunction "1_1") (pintype "passive"))
      (node (ref "C30") (pin "1") (pinfunction "1_1") (pintype "passive"))
      (node (ref "C33") (pin "1") (pinfunction "1_1") (pintype "passive"))
      (node (ref "C35") (pin "2") (pinfunction "2_2") (pintype "passive"))
      (node (ref "D2") (pin "C") (pinfunction "C_C") (pintype "passive"))
      (node (ref "R31") (pin "2") (pinfunction "2_2") (pintype "passive"))
      (node (ref "R32") (pin "1") (pinfunction "E_1") (pintype "passive"))
      (node (ref "U10") (pin "7") (pinfunction "+VS_7") (pintype "input"))
      (node (ref "U6") (pin "4") (pinfunction "V+_4") (pintype "power_in"))
      (node (ref "U8") (pin "1") (pinfunction "OUT_1") (pintype "passive"))
      (node (ref "U9") (pin "7") (pinfunction "+VS_7") (pintype "input"))
      (node (ref "V2+") (pin "1") (pinfunction "1_1") (pintype "passive"))
    )
    (net (code "45") (name "V2-") (class "Default")
      (node (ref "C22") (pin "1") (pinfunction "1_1") (pintype "passive"))
      (node (ref "C31") (pin "1") (pinfunction "1_1") (pintype "passive"))
      (node (ref "C32") (pin "1") (pinfunction "1_1") (pintype "passive"))
      (node (ref "C34") (pin "2") (pinfunction "2_2") (pintype "passive"))
      (node (ref "R30") (pin "1") (pinfunction "1_1") (pintype "passive"))
      (node (ref "R32") (pin "3") (pinfunction "A_3") (pintype "passive"))
      (node (ref "U10") (pin "4") (pinfunction "-VS_4") (pintype "input"))
      (node (ref "U6") (pin "13") (pinfunction "V-_13") (pintype "power_in"))
      (node (ref "U7") (pin "3") (pinfunction "OUT_3") (pintype "passive"))
      (node (ref "U9") (pin "4") (pinfunction "-VS_4") (pintype "input"))
      (node (ref "V2-") (pin "1") (pinfunction "1_1") (pintype "passive"))
    )
    (net (code "46") (name "VIN+") (class "Default")
      (node (ref "C23") (pin "1") (pinfunction "1_1") (pintype "passive"))
      (node (ref "C3") (pin "1") (pinfunction "1_1") (pintype "passive"))
      (node (ref "J3") (pin "1A") (pinfunction "P$1_1A") (pintype "bidirectional"))
      (node (ref "J3") (pin "1B") (pinfunction "P$1_1B") (pintype "bidirectional"))
      (node (ref "J9") (pin "1A") (pinfunction "P$1_1A") (pintype "bidirectional"))
      (node (ref "J9") (pin "1B") (pinfunction "P$1_1B") (pintype "bidirectional"))
      (node (ref "U1") (pin "3") (pinfunction "IN_3") (pintype "input"))
      (node (ref "U8") (pin "3") (pinfunction "IN_3") (pintype "input"))
    )
    (net (code "47") (name "VIN-") (class "Default")
      (node (ref "C1") (pin "2") (pinfunction "2_2") (pintype "passive"))
      (node (ref "C21") (pin "2") (pinfunction "2_2") (pintype "passive"))
      (node (ref "J1") (pin "2") (pinfunction "P$3_2") (pintype "bidirectional"))
      (node (ref "J10") (pin "2") (pinfunction "P$3_2") (pintype "bidirectional"))
      (node (ref "U3") (pin "2") (pinfunction "IN_2") (pintype "input"))
      (node (ref "U3") (pin "2@1") (pinfunction "IN_2@1") (pintype "input"))
      (node (ref "U7") (pin "2") (pinfunction "IN_2") (pintype "input"))
      (node (ref "U7") (pin "2@1") (pinfunction "IN_2@1") (pintype "input"))
    )
    (net (code "48") (name "unconnected-(J1-P$2-Pad3)") (class "Default")
      (node (ref "J1") (pin "3") (pinfunction "P$2_3") (pintype "bidirectional"))
    )
    (net (code "49") (name "unconnected-(J3-P$2-Pad3)") (class "Default")
      (node (ref "J3") (pin "3") (pinfunction "P$2_3") (pintype "bidirectional"))
    )
    (net (code "50") (name "unconnected-(J9-P$2-Pad3)") (class "Default")
      (node (ref "J9") (pin "3") (pinfunction "P$2_3") (pintype "bidirectional"))
    )
    (net (code "51") (name "unconnected-(J10-P$2-Pad3)") (class "Default")
      (node (ref "J10") (pin "3") (pinfunction "P$2_3") (pintype "bidirectional"))
    )
  )
)
